# 02-ORIN_LOW_SPEED_SIGNAL.net
KiCad netlist of a schematic drawn in Altium Designer
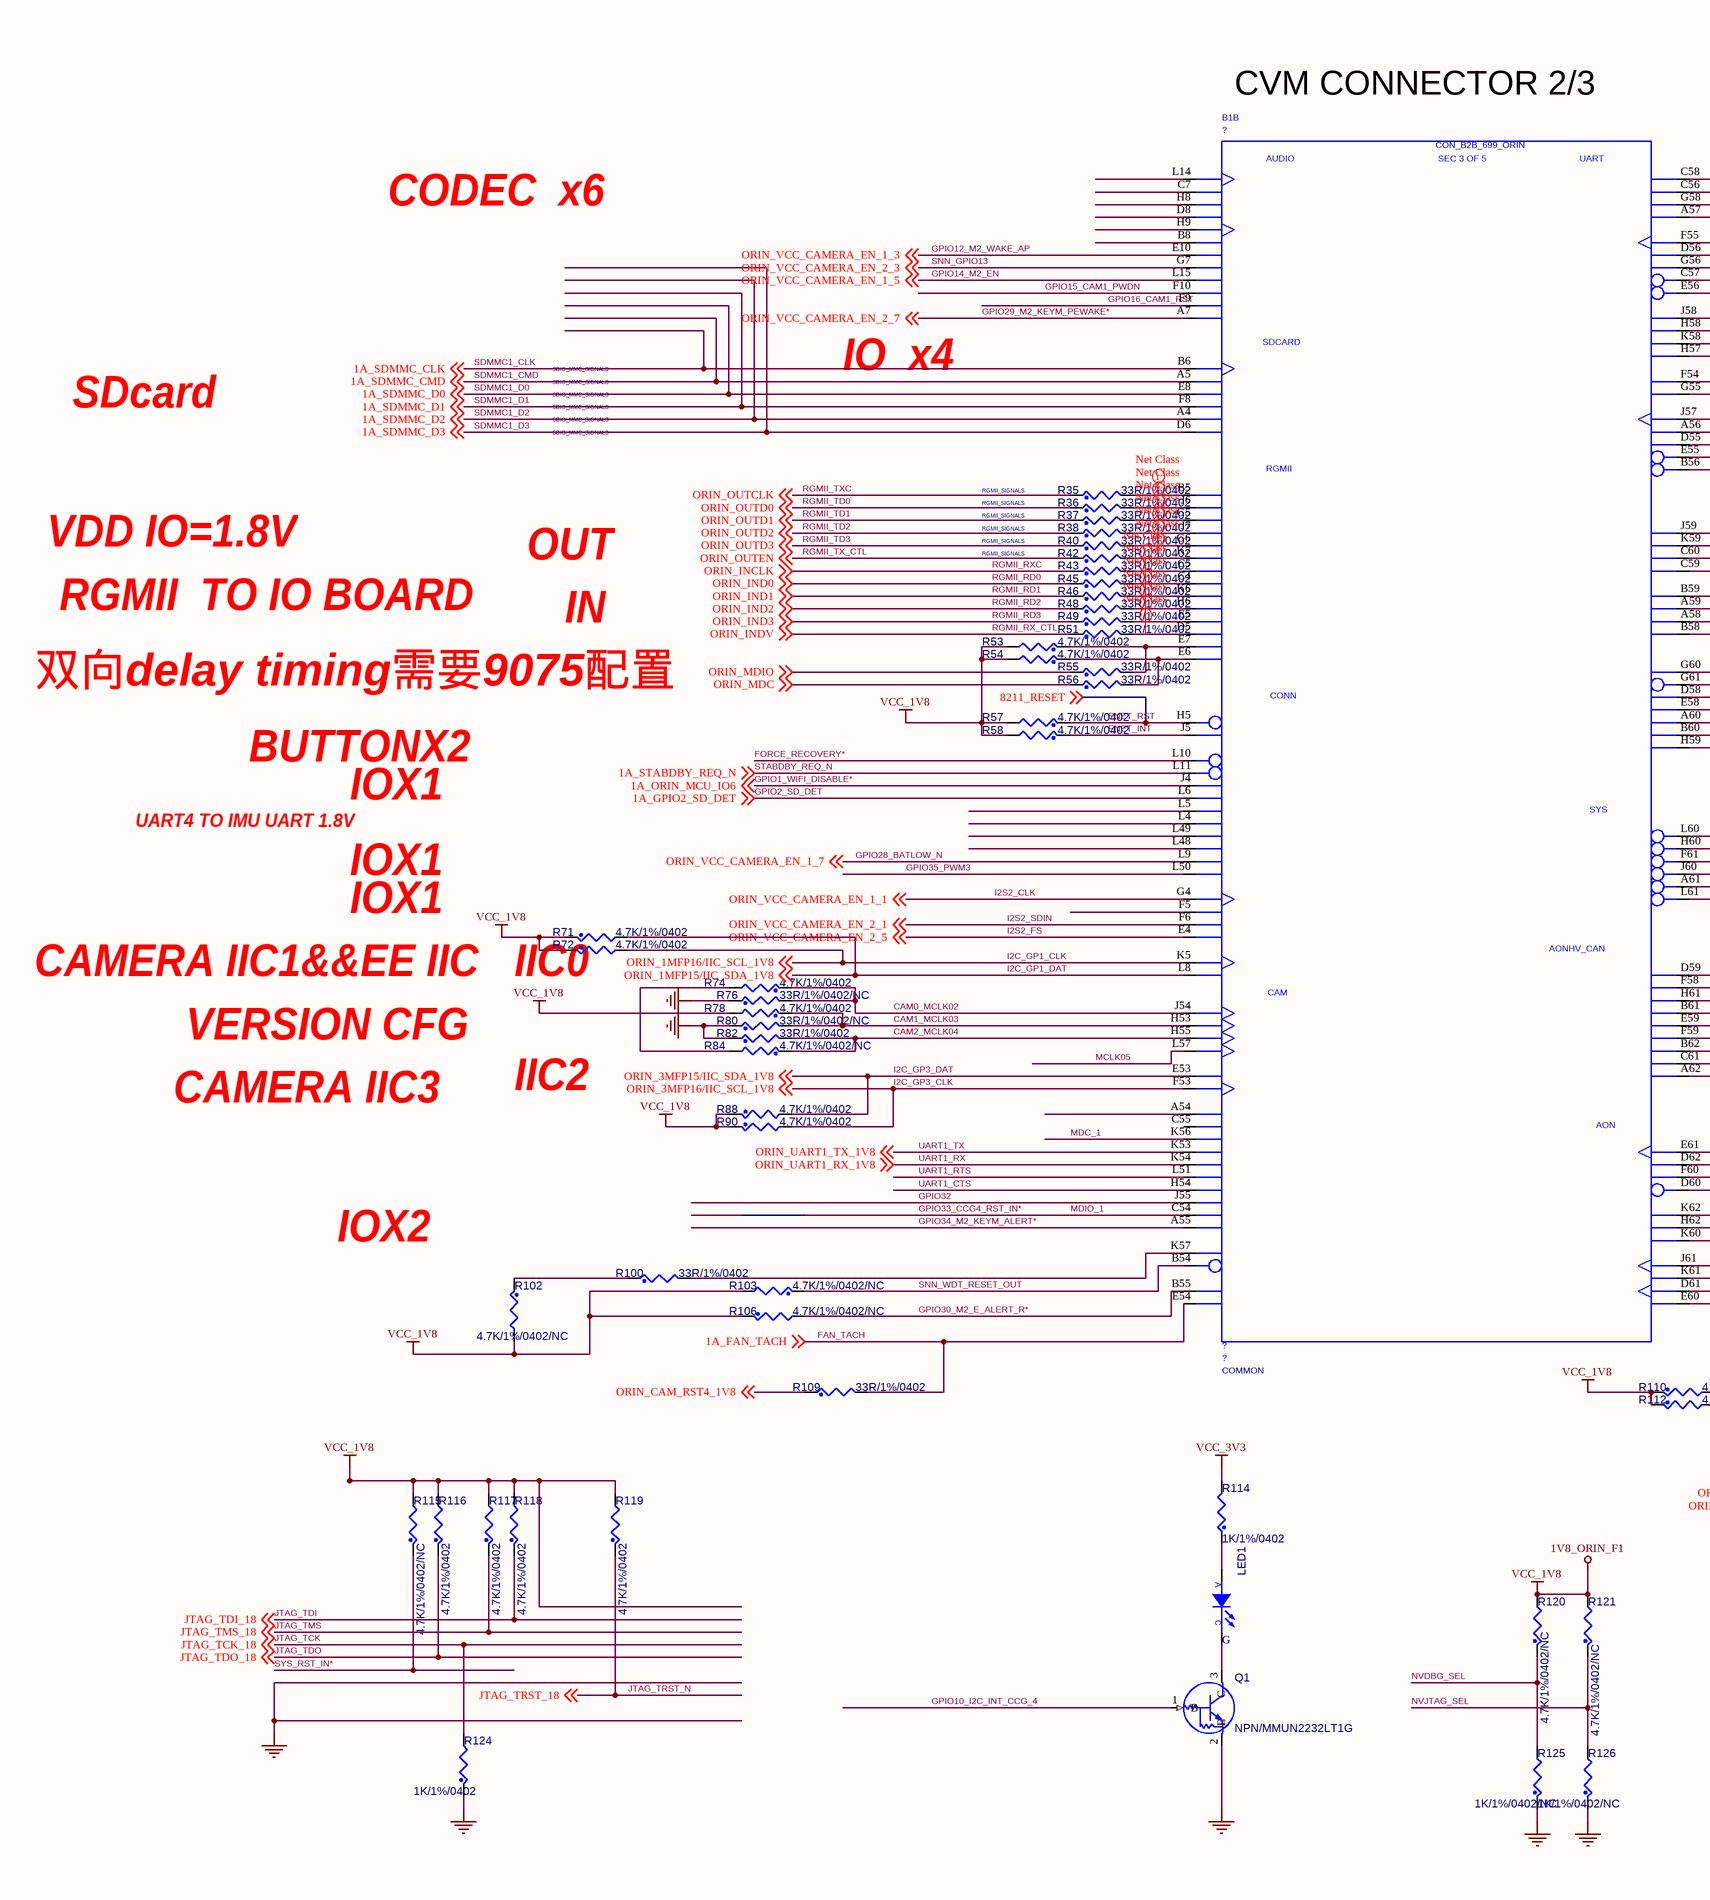
[diagram p0: 02-ORIN_LOW_SPEED_SIGNAL.SchDoc, left]
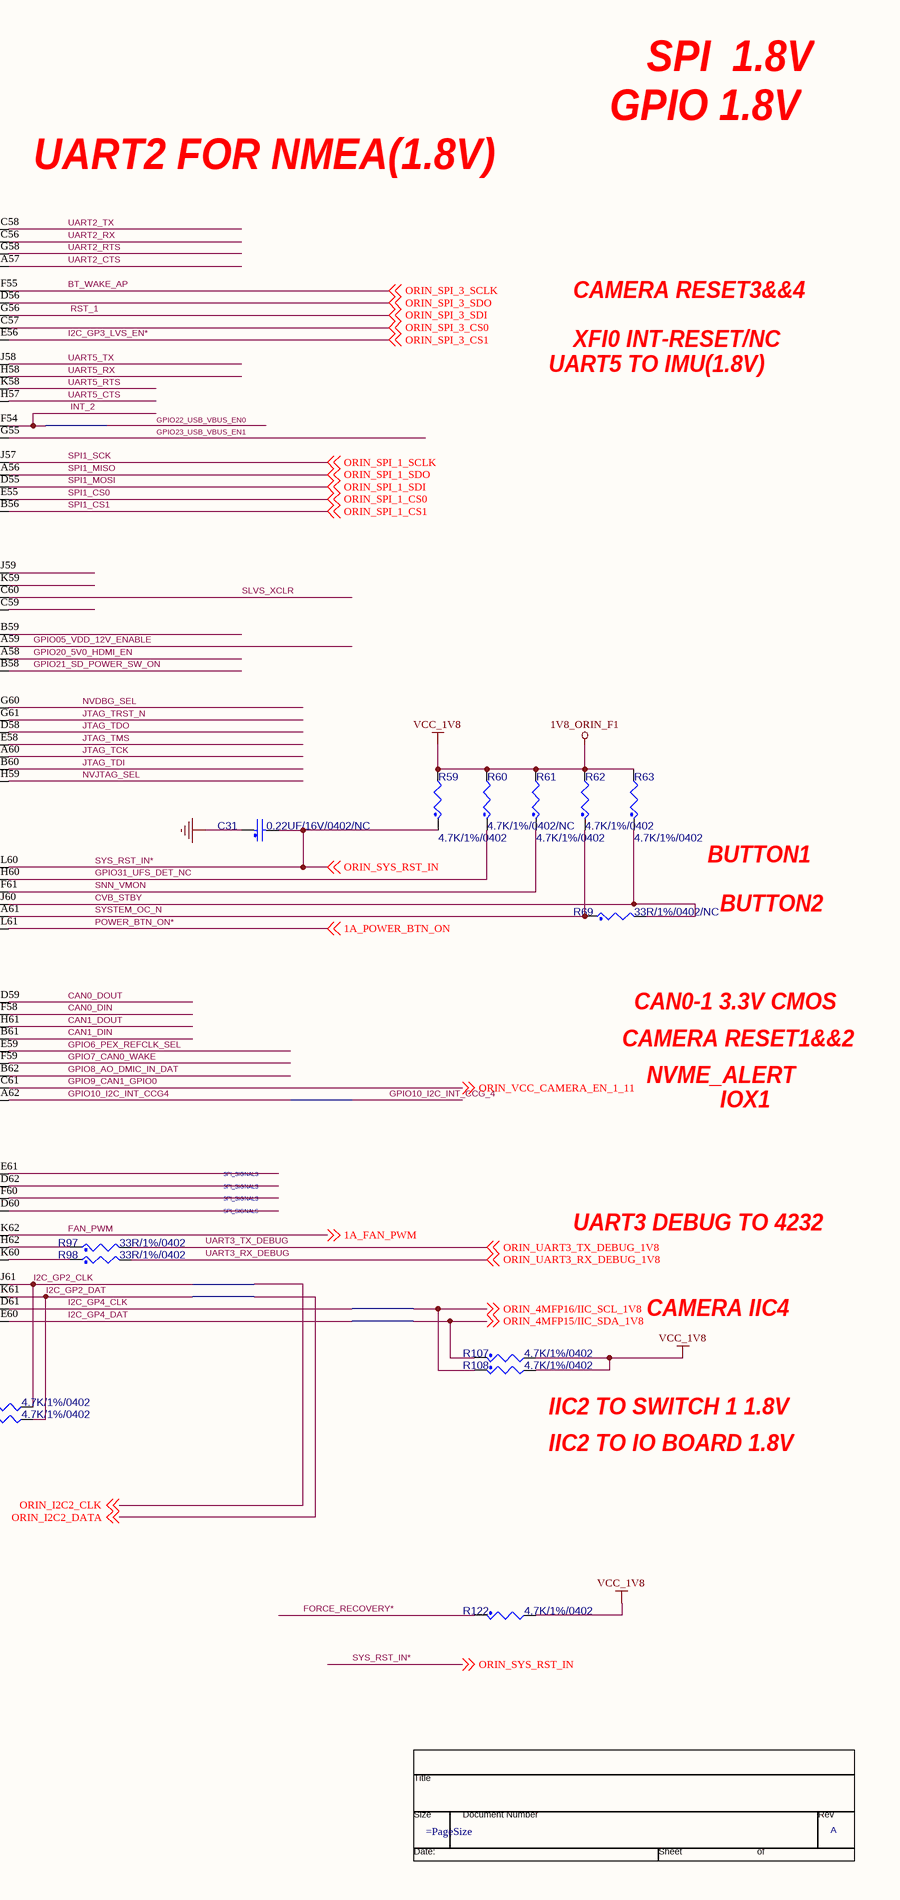
[diagram p1: 02-ORIN_LOW_SPEED_SIGNAL.SchDoc, right]

(export (version "E")
  (design (tool "Eeschema 10.0.6"))
  (components
    (comp (ref "B1")
      (value "CON_B2B_699_ORIN")
      (footprint "CON_MIRMEZ_699_BGA_ST_P009_P013_P015_REVERSE")
      (description "2034560003/MOLEX")
      (fields
        (field (name "DEVICE") "CON_B2B_699_ORIN")
        (field (name "NV_PN") "?")
        (field (name "PACK_TYPE") "?")
        (field (name "PATH") "?")
        (field (name "SKU") "COMMON")
      )
      (libsource (lib "*") (part "CON_B2B_699"))
    )
    (comp (ref "C31")
      (value "0.22UF/16V/0402/NC")
      (footprint "C0402")
      (description "GCM155R71C224KE02/MURATA")
      (fields (field (name "VOLTAGE") "16V") (field (name "TOLERANCE") "10%"))
      (libsource (lib "*") (part "CAP_NP"))
    )
    (comp (ref "LED1")
      (value "LED_P2_Dup1")
      (footprint "LED0603")
      (description "NCD0603G1/NATIONSTAR")
      (fields
        (field (name "VALUE1") "G")
        (field (name "MFR PART NUMBER") "亿光_19-213/G6C-BM1N2B/3T")
        (field (name "PART NUMBER") "20.31.00.0001.02")
      )
      (libsource (lib "*") (part "LED_P2_Dup1"))
    )
    (comp (ref "Q1")
      (value "NPN/MMUN2232LT1G")
      (footprint "SOT23-3-MMUN2232LT1G")
      (description "MMUN2232LT1G/ONSEMI")
      (fields (field (name "Comment") "DTC143ZE"))
      (libsource (lib "*") (part "DTC143ZE"))
    )
    (comp (ref "R35")
      (value "33R/1%/0402")
      (footprint "R0402")
      (description "AC0402FR-0733RL/YAGEO")
      (fields (field (name "TOLERANCE") "1%") (field (name "Comment") "RES_Dup2"))
      (libsource (lib "*") (part "RES_Dup2"))
    )
    (comp (ref "R36")
      (value "33R/1%/0402")
      (footprint "R0402")
      (description "AC0402FR-0733RL/YAGEO")
      (fields (field (name "TOLERANCE") "1%") (field (name "Comment") "RES_Dup2"))
      (libsource (lib "*") (part "RES_Dup2"))
    )
    (comp (ref "R37")
      (value "33R/1%/0402")
      (footprint "R0402")
      (description "AC0402FR-0733RL/YAGEO")
      (fields (field (name "TOLERANCE") "1%") (field (name "Comment") "RES_Dup2"))
      (libsource (lib "*") (part "RES_Dup2"))
    )
    (comp (ref "R38")
      (value "33R/1%/0402")
      (footprint "R0402")
      (description "AC0402FR-0733RL/YAGEO")
      (fields (field (name "TOLERANCE") "1%") (field (name "Comment") "RES_Dup2"))
      (libsource (lib "*") (part "RES_Dup2"))
    )
    (comp (ref "R40")
      (value "33R/1%/0402")
      (footprint "R0402")
      (description "AC0402FR-0733RL/YAGEO")
      (fields (field (name "TOLERANCE") "1%") (field (name "Comment") "RES_Dup2"))
      (libsource (lib "*") (part "RES_Dup2"))
    )
    (comp (ref "R42")
      (value "33R/1%/0402")
      (footprint "R0402")
      (description "AC0402FR-0733RL/YAGEO")
      (fields (field (name "TOLERANCE") "1%") (field (name "Comment") "RES_Dup2"))
      (libsource (lib "*") (part "RES_Dup2"))
    )
    (comp (ref "R43")
      (value "33R/1%/0402")
      (footprint "R0402")
      (description "AC0402FR-0733RL/YAGEO")
      (fields (field (name "TOLERANCE") "1%") (field (name "Comment") "RES_Dup2"))
      (libsource (lib "*") (part "RES_Dup2"))
    )
    (comp (ref "R45")
      (value "33R/1%/0402")
      (footprint "R0402")
      (description "AC0402FR-0733RL/YAGEO")
      (fields (field (name "TOLERANCE") "1%") (field (name "Comment") "RES_Dup2"))
      (libsource (lib "*") (part "RES_Dup2"))
    )
    (comp (ref "R46")
      (value "33R/1%/0402")
      (footprint "R0402")
      (description "AC0402FR-0733RL/YAGEO")
      (fields (field (name "TOLERANCE") "1%") (field (name "Comment") "RES_Dup2"))
      (libsource (lib "*") (part "RES_Dup2"))
    )
    (comp (ref "R48")
      (value "33R/1%/0402")
      (footprint "R0402")
      (description "AC0402FR-0733RL/YAGEO")
      (fields (field (name "TOLERANCE") "1%") (field (name "Comment") "RES_Dup2"))
      (libsource (lib "*") (part "RES_Dup2"))
    )
    (comp (ref "R49")
      (value "33R/1%/0402")
      (footprint "R0402")
      (description "AC0402FR-0733RL/YAGEO")
      (fields (field (name "TOLERANCE") "1%") (field (name "Comment") "RES_Dup2"))
      (libsource (lib "*") (part "RES_Dup2"))
    )
    (comp (ref "R51")
      (value "33R/1%/0402")
      (footprint "R0402")
      (description "AC0402FR-0733RL/YAGEO")
      (fields (field (name "TOLERANCE") "1%") (field (name "Comment") "RES_Dup2"))
      (libsource (lib "*") (part "RES_Dup2"))
    )
    (comp (ref "R53")
      (value "4.7K/1%/0402")
      (footprint "R0402")
      (description "AC0402FR-074K7L/YAGEO")
      (fields (field (name "TOLERANCE") "5%") (field (name "Comment") "RES_Dup2"))
      (libsource (lib "*") (part "RES_Dup2"))
    )
    (comp (ref "R54")
      (value "4.7K/1%/0402")
      (footprint "R0402")
      (description "AC0402FR-074K7L/YAGEO")
      (fields (field (name "TOLERANCE") "5%") (field (name "Comment") "RES_Dup2"))
      (libsource (lib "*") (part "RES_Dup2"))
    )
    (comp (ref "R55")
      (value "33R/1%/0402")
      (footprint "R0402")
      (description "AC0402FR-0733RL/YAGEO")
      (fields (field (name "TOLERANCE") "1%") (field (name "Comment") "RES_Dup2"))
      (libsource (lib "*") (part "RES_Dup2"))
    )
    (comp (ref "R56")
      (value "33R/1%/0402")
      (footprint "R0402")
      (description "AC0402FR-0733RL/YAGEO")
      (fields (field (name "TOLERANCE") "1%") (field (name "Comment") "RES_Dup2"))
      (libsource (lib "*") (part "RES_Dup2"))
    )
    (comp (ref "R57")
      (value "4.7K/1%/0402")
      (footprint "R0402")
      (description "AC0402FR-074K7L/YAGEO")
      (fields (field (name "TOLERANCE") "5%") (field (name "Comment") "RES_Dup2"))
      (libsource (lib "*") (part "RES_Dup2"))
    )
    (comp (ref "R58")
      (value "4.7K/1%/0402")
      (footprint "R0402")
      (description "AC0402FR-074K7L/YAGEO")
      (fields (field (name "TOLERANCE") "5%") (field (name "Comment") "RES_Dup2"))
      (libsource (lib "*") (part "RES_Dup2"))
    )
    (comp (ref "R59")
      (value "4.7K/1%/0402")
      (footprint "R0402")
      (description "AC0402FR-074K7L/YAGEO")
      (fields (field (name "TOLERANCE") "5%") (field (name "Comment") "RES_Dup2"))
      (libsource (lib "*") (part "RES_Dup2"))
    )
    (comp (ref "R60")
      (value "4.7K/1%/0402/NC")
      (footprint "R0402")
      (description "AC0402FR-074K7L/YAGEO")
      (fields (field (name "TOLERANCE") "5%") (field (name "Comment") "RES_Dup2"))
      (libsource (lib "*") (part "RES_Dup2"))
    )
    (comp (ref "R61")
      (value "4.7K/1%/0402")
      (footprint "R0402")
      (description "AC0402FR-074K7L/YAGEO")
      (fields (field (name "TOLERANCE") "5%") (field (name "Comment") "RES_Dup2"))
      (libsource (lib "*") (part "RES_Dup2"))
    )
    (comp (ref "R62")
      (value "4.7K/1%/0402")
      (footprint "R0402")
      (description "AC0402FR-074K7L/YAGEO")
      (fields (field (name "TOLERANCE") "5%") (field (name "Comment") "RES_Dup2"))
      (libsource (lib "*") (part "RES_Dup2"))
    )
    (comp (ref "R63")
      (value "4.7K/1%/0402")
      (footprint "R0402")
      (description "AC0402FR-074K7L/YAGEO")
      (fields (field (name "TOLERANCE") "5%") (field (name "Comment") "RES_Dup2"))
      (libsource (lib "*") (part "RES_Dup2"))
    )
    (comp (ref "R69")
      (value "33R/1%/0402/NC")
      (footprint "R0402")
      (description "AC0402FR-0733RL/YAGEO")
      (fields (field (name "TOLERANCE") "1%") (field (name "Comment") "RES_Dup2"))
      (libsource (lib "*") (part "RES_Dup2"))
    )
    (comp (ref "R71")
      (value "4.7K/1%/0402")
      (footprint "R0402")
      (description "AC0402FR-074K7L/YAGEO")
      (fields (field (name "TOLERANCE") "5%") (field (name "Comment") "RES_Dup2"))
      (libsource (lib "*") (part "RES_Dup2"))
    )
    (comp (ref "R72")
      (value "4.7K/1%/0402")
      (footprint "R0402")
      (description "AC0402FR-074K7L/YAGEO")
      (fields (field (name "TOLERANCE") "5%") (field (name "Comment") "RES_Dup2"))
      (libsource (lib "*") (part "RES_Dup2"))
    )
    (comp (ref "R74")
      (value "4.7K/1%/0402")
      (footprint "R0402")
      (description "AC0402FR-074K7L/YAGEO")
      (fields (field (name "TOLERANCE") "5%") (field (name "Comment") "RES_Dup2"))
      (libsource (lib "*") (part "RES_Dup2"))
    )
    (comp (ref "R76")
      (value "33R/1%/0402/NC")
      (footprint "R0402")
      (description "AC0402FR-0733RL/YAGEO")
      (fields (field (name "TOLERANCE") "1%") (field (name "Comment") "RES_Dup2"))
      (libsource (lib "*") (part "RES_Dup2"))
    )
    (comp (ref "R78")
      (value "4.7K/1%/0402")
      (footprint "R0402")
      (description "AC0402FR-074K7L/YAGEO")
      (fields (field (name "TOLERANCE") "5%") (field (name "Comment") "RES_Dup2"))
      (libsource (lib "*") (part "RES_Dup2"))
    )
    (comp (ref "R80")
      (value "33R/1%/0402/NC")
      (footprint "R0402")
      (description "AC0402FR-0733RL/YAGEO")
      (fields (field (name "TOLERANCE") "1%") (field (name "Comment") "RES_Dup2"))
      (libsource (lib "*") (part "RES_Dup2"))
    )
    (comp (ref "R82")
      (value "33R/1%/0402")
      (footprint "R0402")
      (description "AC0402FR-0733RL/YAGEO")
      (fields (field (name "TOLERANCE") "1%") (field (name "Comment") "RES_Dup2"))
      (libsource (lib "*") (part "RES_Dup2"))
    )
    (comp (ref "R84")
      (value "4.7K/1%/0402/NC")
      (footprint "R0402")
      (description "AC0402FR-074K7L/YAGEO")
      (fields (field (name "TOLERANCE") "5%") (field (name "Comment") "RES_Dup2"))
      (libsource (lib "*") (part "RES_Dup2"))
    )
    (comp (ref "R88")
      (value "4.7K/1%/0402")
      (footprint "R0402")
      (description "AC0402FR-074K7L/YAGEO")
      (fields (field (name "TOLERANCE") "5%") (field (name "Comment") "RES_Dup2"))
      (libsource (lib "*") (part "RES_Dup2"))
    )
    (comp (ref "R90")
      (value "4.7K/1%/0402")
      (footprint "R0402")
      (description "AC0402FR-074K7L/YAGEO")
      (fields (field (name "TOLERANCE") "5%") (field (name "Comment") "RES_Dup2"))
      (libsource (lib "*") (part "RES_Dup2"))
    )
    (comp (ref "R97")
      (value "33R/1%/0402")
      (footprint "R0402")
      (description "AC0402FR-0733RL/YAGEO")
      (fields (field (name "TOLERANCE") "1%") (field (name "Comment") "RES_Dup2"))
      (libsource (lib "*") (part "RES_Dup2"))
    )
    (comp (ref "R98")
      (value "33R/1%/0402")
      (footprint "R0402")
      (description "AC0402FR-0733RL/YAGEO")
      (fields (field (name "TOLERANCE") "1%") (field (name "Comment") "RES_Dup2"))
      (libsource (lib "*") (part "RES_Dup2"))
    )
    (comp (ref "R100")
      (value "33R/1%/0402")
      (footprint "R0402")
      (description "AC0402FR-0733RL/YAGEO")
      (fields (field (name "TOLERANCE") "1%") (field (name "Comment") "RES_Dup2"))
      (libsource (lib "*") (part "RES_Dup2"))
    )
    (comp (ref "R102")
      (value "4.7K/1%/0402/NC")
      (footprint "R0402")
      (description "AC0402FR-074K7L/YAGEO")
      (fields (field (name "TOLERANCE") "5%") (field (name "Comment") "RES_Dup2"))
      (libsource (lib "*") (part "RES_Dup2"))
    )
    (comp (ref "R103")
      (value "4.7K/1%/0402/NC")
      (footprint "R0402")
      (description "AC0402FR-074K7L/YAGEO")
      (fields (field (name "TOLERANCE") "5%") (field (name "Comment") "RES_Dup2"))
      (libsource (lib "*") (part "RES_Dup2"))
    )
    (comp (ref "R106")
      (value "4.7K/1%/0402/NC")
      (footprint "R0402")
      (description "AC0402FR-074K7L/YAGEO")
      (fields (field (name "TOLERANCE") "5%") (field (name "Comment") "RES_Dup2"))
      (libsource (lib "*") (part "RES_Dup2"))
    )
    (comp (ref "R107")
      (value "4.7K/1%/0402")
      (footprint "R0402")
      (description "AC0402FR-074K7L/YAGEO")
      (fields (field (name "TOLERANCE") "5%") (field (name "Comment") "RES_Dup2"))
      (libsource (lib "*") (part "RES_Dup2"))
    )
    (comp (ref "R108")
      (value "4.7K/1%/0402")
      (footprint "R0402")
      (description "AC0402FR-074K7L/YAGEO")
      (fields (field (name "TOLERANCE") "5%") (field (name "Comment") "RES_Dup2"))
      (libsource (lib "*") (part "RES_Dup2"))
    )
    (comp (ref "R109")
      (value "33R/1%/0402")
      (footprint "R0402")
      (description "AC0402FR-0733RL/YAGEO")
      (fields (field (name "TOLERANCE") "1%") (field (name "Comment") "RES_Dup2"))
      (libsource (lib "*") (part "RES_Dup2"))
    )
    (comp (ref "R110")
      (value "4.7K/1%/0402")
      (footprint "R0402")
      (description "AC0402FR-074K7L/YAGEO")
      (fields (field (name "TOLERANCE") "5%") (field (name "Comment") "RES_Dup2"))
      (libsource (lib "*") (part "RES_Dup2"))
    )
    (comp (ref "R112")
      (value "4.7K/1%/0402")
      (footprint "R0402")
      (description "AC0402FR-074K7L/YAGEO")
      (fields (field (name "TOLERANCE") "5%") (field (name "Comment") "RES_Dup2"))
      (libsource (lib "*") (part "RES_Dup2"))
    )
    (comp (ref "R114")
      (value "1K/1%/0402")
      (footprint "R0402")
      (description "AC0402FR-071KL/YAGEO")
      (fields (field (name "TOLERANCE") "5%") (field (name "Comment") "RES_Dup2"))
      (libsource (lib "*") (part "RES_Dup2"))
    )
    (comp (ref "R115")
      (value "4.7K/1%/0402/NC")
      (footprint "R0402")
      (description "AC0402FR-074K7L/YAGEO")
      (fields (field (name "TOLERANCE") "5%") (field (name "Comment") "RES_Dup2"))
      (libsource (lib "*") (part "RES_Dup2"))
    )
    (comp (ref "R116")
      (value "4.7K/1%/0402")
      (footprint "R0402")
      (description "AC0402FR-074K7L/YAGEO")
      (fields (field (name "TOLERANCE") "5%") (field (name "Comment") "RES_Dup2"))
      (libsource (lib "*") (part "RES_Dup2"))
    )
    (comp (ref "R117")
      (value "4.7K/1%/0402")
      (footprint "R0402")
      (description "AC0402FR-074K7L/YAGEO")
      (fields (field (name "TOLERANCE") "5%") (field (name "Comment") "RES_Dup2"))
      (libsource (lib "*") (part "RES_Dup2"))
    )
    (comp (ref "R118")
      (value "4.7K/1%/0402")
      (footprint "R0402")
      (description "AC0402FR-074K7L/YAGEO")
      (fields (field (name "TOLERANCE") "5%") (field (name "Comment") "RES_Dup2"))
      (libsource (lib "*") (part "RES_Dup2"))
    )
    (comp (ref "R119")
      (value "4.7K/1%/0402")
      (footprint "R0402")
      (description "AC0402FR-074K7L/YAGEO")
      (fields (field (name "TOLERANCE") "5%") (field (name "Comment") "RES_Dup2"))
      (libsource (lib "*") (part "RES_Dup2"))
    )
    (comp (ref "R120")
      (value "4.7K/1%/0402/NC")
      (footprint "R0402")
      (description "AC0402FR-074K7L/YAGEO")
      (fields (field (name "TOLERANCE") "5%") (field (name "Comment") "RES_Dup2"))
      (libsource (lib "*") (part "RES_Dup2"))
    )
    (comp (ref "R121")
      (value "4.7K/1%/0402/NC")
      (footprint "R0402")
      (description "AC0402FR-074K7L/YAGEO")
      (fields (field (name "TOLERANCE") "5%") (field (name "Comment") "RES_Dup2"))
      (libsource (lib "*") (part "RES_Dup2"))
    )
    (comp (ref "R122")
      (value "4.7K/1%/0402")
      (footprint "R0402")
      (description "AC0402FR-074K7L/YAGEO")
      (fields (field (name "TOLERANCE") "5%") (field (name "Comment") "RES_Dup2"))
      (libsource (lib "*") (part "RES_Dup2"))
    )
    (comp (ref "R124")
      (value "1K/1%/0402")
      (footprint "R0402")
      (description "AC0402FR-071KL/YAGEO")
      (fields (field (name "TOLERANCE") "5%") (field (name "Comment") "RES_Dup2"))
      (libsource (lib "*") (part "RES_Dup2"))
    )
    (comp (ref "R125")
      (value "1K/1%/0402/NC")
      (footprint "R0402")
      (description "AC0402FR-071KL/YAGEO")
      (fields (field (name "TOLERANCE") "5%") (field (name "Comment") "RES_Dup2"))
      (libsource (lib "*") (part "RES_Dup2"))
    )
    (comp (ref "R126")
      (value "1K/1%/0402/NC")
      (footprint "R0402")
      (description "AC0402FR-071KL/YAGEO")
      (fields (field (name "TOLERANCE") "5%") (field (name "Comment") "RES_Dup2"))
      (libsource (lib "*") (part "RES_Dup2"))
    )
  )
  (nets
    (net (code "1") (name "/CAM0_MCLK02") (class "Default")
      (node (ref "B1") (pin "J54") (pinfunction "MCLK02_J54") (pintype "bidirectional"))
      (node (ref "R74") (pin "1") (pinfunction "1_1") (pintype "passive"))
      (node (ref "R76") (pin "2") (pinfunction "2_2") (pintype "passive"))
    )
    (net (code "2") (name "/CAM1_MCLK03") (class "Default")
      (node (ref "B1") (pin "H53") (pinfunction "MCLK03_H53") (pintype "bidirectional"))
      (node (ref "R78") (pin "1") (pinfunction "1_1") (pintype "passive"))
      (node (ref "R80") (pin "2") (pinfunction "2_2") (pintype "passive"))
    )
    (net (code "3") (name "/CAM2_MCLK04") (class "Default")
      (node (ref "B1") (pin "H55") (pinfunction "MCLK04_H55") (pintype "bidirectional"))
      (node (ref "R82") (pin "2") (pinfunction "2_2") (pintype "passive"))
      (node (ref "R84") (pin "1") (pinfunction "1_1") (pintype "passive"))
    )
    (net (code "4") (name "/CAN0_DIN") (class "Default")
      (node (ref "B1") (pin "F58") (pinfunction "CAN0_DIN_F58") (pintype "bidirectional"))
    )
    (net (code "5") (name "/CAN0_DOUT") (class "Default")
      (node (ref "B1") (pin "D59") (pinfunction "CAN0_DOUT_D59") (pintype "bidirectional"))
    )
    (net (code "6") (name "/CAN1_DIN") (class "Default")
      (node (ref "B1") (pin "B61") (pinfunction "CAN1_DIN_B61") (pintype "bidirectional"))
    )
    (net (code "7") (name "/CAN1_DOUT") (class "Default")
      (node (ref "B1") (pin "H61") (pinfunction "CAN1_DOUT_H61") (pintype "bidirectional"))
    )
    (net (code "8") (name "/CVB_STBY") (class "Default")
      (node (ref "B1") (pin "J60") (pinfunction "STANDBY_ACK_N_J60") (pintype "bidirectional"))
      (node (ref "R63") (pin "1") (pinfunction "1_1") (pintype "passive"))
      (node (ref "R69") (pin "2") (pinfunction "2_2") (pintype "passive"))
    )
    (net (code "9") (name "/ENET_INT") (class "Default")
      (node (ref "B1") (pin "J5") (pinfunction "ENET_INT_J5") (pintype "bidirectional"))
      (node (ref "R58") (pin "1") (pinfunction "1_1") (pintype "passive"))
    )
    (net (code "10") (name "/FORCE_RECOVERY*") (class "Default")
      (node (ref "B1") (pin "L10") (pinfunction "FORCE_RECOVERY_N_L10") (pintype "bidirectional"))
      (node (ref "R122") (pin "1") (pinfunction "1_1") (pintype "passive"))
    )
    (net (code "11") (name "/GPIO05_VDD_12V_ENABLE") (class "Default")
      (node (ref "B1") (pin "A59") (pinfunction "GPIO05_A59") (pintype "bidirectional"))
    )
    (net (code "12") (name "/GPIO6_PEX_REFCLK_SEL") (class "Default")
      (node (ref "B1") (pin "E59") (pinfunction "GPIO06_E59") (pintype "bidirectional"))
    )
    (net (code "13") (name "/GPIO7_CAN0_WAKE") (class "Default")
      (node (ref "B1") (pin "F59") (pinfunction "GPIO07_F59") (pintype "bidirectional"))
    )
    (net (code "14") (name "/GPIO8_AO_DMIC_IN_DAT") (class "Default")
      (node (ref "B1") (pin "B62") (pinfunction "GPIO08_B62") (pintype "bidirectional"))
    )
    (net (code "15") (name "/GPIO10_I2C_INT_CCG4") (class "Default")
      (node (ref "B1") (pin "A62") (pinfunction "GPIO10_A62") (pintype "bidirectional"))
      (node (ref "Q1") (pin "1") (pinfunction "B_1") (pintype "input"))
    )
    (net (code "16") (name "/GPIO15_CAM1_PWDN") (class "Default")
      (node (ref "B1") (pin "F10") (pinfunction "GPIO15_F10") (pintype "bidirectional"))
    )
    (net (code "17") (name "/GPIO16_CAM1_RST") (class "Default")
      (node (ref "B1") (pin "F9") (pinfunction "GPIO16_F9") (pintype "bidirectional"))
    )
    (net (code "18") (name "/GPIO20_5V0_HDMI_EN") (class "Default")
      (node (ref "B1") (pin "A58") (pinfunction "GPIO20_A58") (pintype "bidirectional"))
    )
    (net (code "19") (name "/GPIO21_SD_POWER_SW_ON") (class "Default")
      (node (ref "B1") (pin "B58") (pinfunction "GPIO21_B58") (pintype "bidirectional"))
    )
    (net (code "20") (name "/GPIO22_USB_VBUS_EN0") (class "Default")
      (node (ref "B1") (pin "F54") (pinfunction "GPIO22_F54") (pintype "bidirectional"))
    )
    (net (code "21") (name "/GPIO23_USB_VBUS_EN1") (class "Default")
      (node (ref "B1") (pin "G55") (pinfunction "GPIO23_G55") (pintype "bidirectional"))
    )
    (net (code "22") (name "/GPIO30_M2_E_ALERT_R*") (class "Default")
      (node (ref "B1") (pin "B55") (pinfunction "GPIO30_B55") (pintype "bidirectional"))
      (node (ref "R106") (pin "2") (pinfunction "2_2") (pintype "passive"))
    )
    (net (code "23") (name "/GPIO31_UFS_DET_NC") (class "Default")
      (node (ref "B1") (pin "H60") (pinfunction "GPIO31_H60") (pintype "bidirectional"))
      (node (ref "R60") (pin "1") (pinfunction "1_1") (pintype "passive"))
    )
    (net (code "24") (name "/GPIO32") (class "Default")
      (node (ref "B1") (pin "J55") (pinfunction "GPIO32_J55") (pintype "bidirectional"))
    )
    (net (code "25") (name "/GPIO33_CCG4_RST_IN*") (class "Default")
      (node (ref "B1") (pin "C54") (pinfunction "GPIO33_C54") (pintype "bidirectional"))
    )
    (net (code "26") (name "/GPIO34_M2_KEYM_ALERT*") (class "Default")
      (node (ref "B1") (pin "A55") (pinfunction "GPIO34_A55") (pintype "bidirectional"))
    )
    (net (code "27") (name "/GPIO35_PWM3") (class "Default")
      (node (ref "B1") (pin "L50") (pinfunction "GPIO35_L50") (pintype "bidirectional"))
    )
    (net (code "28") (name "/MCLK05") (class "Default")
      (node (ref "B1") (pin "L57") (pinfunction "MCLK05_L57") (pintype "bidirectional"))
    )
    (net (code "29") (name "/MDC_1") (class "Default")
      (node (ref "B1") (pin "K56") (pinfunction "GPIO19_K56") (pintype "bidirectional"))
    )
    (net (code "30") (name "/NVDBG_SEL") (class "Default")
      (node (ref "B1") (pin "G60") (pinfunction "NVDBG_SEL_G60") (pintype "bidirectional"))
      (node (ref "R120") (pin "1") (pinfunction "1_1") (pintype "passive"))
      (node (ref "R125") (pin "2") (pinfunction "2_2") (pintype "passive"))
    )
    (net (code "31") (name "/NVJTAG_SEL") (class "Default")
      (node (ref "B1") (pin "H59") (pinfunction "NVJTAG_SEL_H59") (pintype "bidirectional"))
      (node (ref "R121") (pin "1") (pinfunction "1_1") (pintype "passive"))
      (node (ref "R126") (pin "2") (pinfunction "2_2") (pintype "passive"))
    )
    (net (code "32") (name "/SLVS_XCLR") (class "Default")
      (node (ref "B1") (pin "C60") (pinfunction "I2S3_FS_C60") (pintype "bidirectional"))
    )
    (net (code "33") (name "/SNN_VMON") (class "Default")
      (node (ref "B1") (pin "F61") (pinfunction "VCOMP_ALERT_N_F61") (pintype "bidirectional"))
      (node (ref "R61") (pin "1") (pinfunction "1_1") (pintype "passive"))
    )
    (net (code "34") (name "/SNN_WDT_RESET_OUT") (class "Default")
      (node (ref "B1") (pin "B54") (pinfunction "WDT_RESET_OUT_N_B54") (pintype "bidirectional"))
      (node (ref "R103") (pin "1") (pinfunction "1_1") (pintype "passive"))
    )
    (net (code "35") (name "/SYSTEM_OC_N") (class "Default")
      (node (ref "B1") (pin "A61") (pinfunction "SYSTEM_OC_N_A61") (pintype "bidirectional"))
      (node (ref "R62") (pin "1") (pinfunction "1_1") (pintype "passive"))
      (node (ref "R69") (pin "1") (pinfunction "1_1") (pintype "passive"))
    )
    (net (code "36") (name "/UART1_CTS") (class "Default")
      (node (ref "B1") (pin "H54") (pinfunction "UART1_CTS_H54") (pintype "bidirectional"))
    )
    (net (code "37") (name "/UART1_RTS") (class "Default")
      (node (ref "B1") (pin "L51") (pinfunction "UART1_RTS_L51") (pintype "bidirectional"))
    )
    (net (code "38") (name "/UART2_CTS") (class "Default")
      (node (ref "B1") (pin "A57") (pinfunction "UART2_CTS_A57") (pintype "bidirectional"))
    )
    (net (code "39") (name "/UART2_RTS") (class "Default")
      (node (ref "B1") (pin "G58") (pinfunction "UART2_RTS_G58") (pintype "bidirectional"))
    )
    (net (code "40") (name "/UART2_RX") (class "Default")
      (node (ref "B1") (pin "C56") (pinfunction "UART2_RX_C56") (pintype "bidirectional"))
    )
    (net (code "41") (name "/UART2_TX") (class "Default")
      (node (ref "B1") (pin "C58") (pinfunction "UART2_TX_C58") (pintype "bidirectional"))
    )
    (net (code "42") (name "/UART5_CTS") (class "Default")
      (node (ref "B1") (pin "H57") (pinfunction "UART5_CTS_H57") (pintype "bidirectional"))
    )
    (net (code "43") (name "/UART5_RTS") (class "Default")
      (node (ref "B1") (pin "K58") (pinfunction "UART5_RTS_K58") (pintype "bidirectional"))
    )
    (net (code "44") (name "/UART5_RX") (class "Default")
      (node (ref "B1") (pin "H58") (pinfunction "UART5_RX_H58") (pintype "bidirectional"))
    )
    (net (code "45") (name "/UART5_TX") (class "Default")
      (node (ref "B1") (pin "J58") (pinfunction "UART5_TX_J58") (pintype "bidirectional"))
    )
    (net (code "46") (name "1A_FAN_PWM") (class "Default")
      (node (ref "B1") (pin "K62") (pinfunction "FAN_PWM_K62") (pintype "bidirectional"))
    )
    (net (code "47") (name "1A_FAN_TACH") (class "Default")
      (node (ref "B1") (pin "E54") (pinfunction "FAN_TACH_E54") (pintype "bidirectional"))
      (node (ref "R109") (pin "2") (pinfunction "2_2") (pintype "passive"))
    )
    (net (code "48") (name "1A_GPIO2_SD_DET") (class "Default")
      (node (ref "B1") (pin "L6") (pinfunction "GPIO02_L6") (pintype "bidirectional"))
    )
    (net (code "49") (name "1A_ORIN_MCU_IO6") (class "Default")
      (node (ref "B1") (pin "J4") (pinfunction "GPIO01_J4") (pintype "bidirectional"))
    )
    (net (code "50") (name "1A_POWER_BTN_ON") (class "Default")
      (node (ref "B1") (pin "L61") (pinfunction "POWER_BTN_N_L61") (pintype "bidirectional"))
    )
    (net (code "51") (name "1A_SDMMC_CLK") (class "Default")
      (node (ref "B1") (pin "B6") (pinfunction "SDCARD_CLK_B6") (pintype "bidirectional"))
    )
    (net (code "52") (name "1A_SDMMC_CMD") (class "Default")
      (node (ref "B1") (pin "A5") (pinfunction "SDCARD_CMD_A5") (pintype "bidirectional"))
    )
    (net (code "53") (name "1A_SDMMC_D0") (class "Default")
      (node (ref "B1") (pin "E8") (pinfunction "SDCARD_D0_E8") (pintype "bidirectional"))
    )
    (net (code "54") (name "1A_SDMMC_D1") (class "Default")
      (node (ref "B1") (pin "F8") (pinfunction "SDCARD_D1_F8") (pintype "bidirectional"))
    )
    (net (code "55") (name "1A_SDMMC_D2") (class "Default")
      (node (ref "B1") (pin "A4") (pinfunction "SDCARD_D2_A4") (pintype "bidirectional"))
    )
    (net (code "56") (name "1A_SDMMC_D3") (class "Default")
      (node (ref "B1") (pin "D6") (pinfunction "SDCARD_D3_D6") (pintype "bidirectional"))
    )
    (net (code "57") (name "1A_STABDBY_REQ_N") (class "Default")
      (node (ref "B1") (pin "L11") (pinfunction "STANDBY_REQ_N_L11") (pintype "bidirectional"))
    )
    (net (code "58") (name "1V8_ORIN_F1") (class "Default")
      (node (ref "R102") (pin "2") (pinfunction "2_2") (pintype "passive"))
      (node (ref "R103") (pin "2") (pinfunction "2_2") (pintype "passive"))
      (node (ref "R106") (pin "1") (pinfunction "1_1") (pintype "passive"))
      (node (ref "R107") (pin "2") (pinfunction "2_2") (pintype "passive"))
      (node (ref "R108") (pin "2") (pinfunction "2_2") (pintype "passive"))
      (node (ref "R110") (pin "1") (pinfunction "1_1") (pintype "passive"))
      (node (ref "R112") (pin "1") (pinfunction "1_1") (pintype "passive"))
      (node (ref "R115") (pin "2") (pinfunction "2_2") (pintype "passive"))
      (node (ref "R116") (pin "2") (pinfunction "2_2") (pintype "passive"))
      (node (ref "R117") (pin "2") (pinfunction "2_2") (pintype "passive"))
      (node (ref "R118") (pin "2") (pinfunction "2_2") (pintype "passive"))
      (node (ref "R119") (pin "2") (pinfunction "2_2") (pintype "passive"))
      (node (ref "R120") (pin "2") (pinfunction "2_2") (pintype "passive"))
      (node (ref "R121") (pin "2") (pinfunction "2_2") (pintype "passive"))
      (node (ref "R122") (pin "2") (pinfunction "2_2") (pintype "passive"))
      (node (ref "R53") (pin "2") (pinfunction "2_2") (pintype "passive"))
      (node (ref "R54") (pin "2") (pinfunction "2_2") (pintype "passive"))
      (node (ref "R57") (pin "2") (pinfunction "2_2") (pintype "passive"))
      (node (ref "R58") (pin "2") (pinfunction "2_2") (pintype "passive"))
      (node (ref "R59") (pin "2") (pinfunction "2_2") (pintype "passive"))
      (node (ref "R60") (pin "2") (pinfunction "2_2") (pintype "passive"))
      (node (ref "R61") (pin "2") (pinfunction "2_2") (pintype "passive"))
      (node (ref "R62") (pin "2") (pinfunction "2_2") (pintype "passive"))
      (node (ref "R63") (pin "2") (pinfunction "2_2") (pintype "passive"))
      (node (ref "R71") (pin "1") (pinfunction "1_1") (pintype "passive"))
      (node (ref "R72") (pin "1") (pinfunction "1_1") (pintype "passive"))
      (node (ref "R78") (pin "2") (pinfunction "2_2") (pintype "passive"))
      (node (ref "R88") (pin "1") (pinfunction "1_1") (pintype "passive"))
      (node (ref "R90") (pin "1") (pinfunction "1_1") (pintype "passive"))
    )
    (net (code "59") (name "8211_RESET") (class "Default")
      (node (ref "B1") (pin "H5") (pinfunction "ENET_RST_N_H5") (pintype "bidirectional"))
      (node (ref "R57") (pin "1") (pinfunction "1_1") (pintype "passive"))
    )
    (net (code "60") (name "GND") (class "Default")
      (node (ref "C31") (pin "1") (pinfunction "1_1") (pintype "passive"))
      (node (ref "Q1") (pin "2") (pinfunction "E_2") (pintype "passive"))
      (node (ref "R124") (pin "1") (pinfunction "1_1") (pintype "passive"))
      (node (ref "R125") (pin "1") (pinfunction "1_1") (pintype "passive"))
      (node (ref "R126") (pin "1") (pinfunction "1_1") (pintype "passive"))
      (node (ref "R76") (pin "1") (pinfunction "1_1") (pintype "passive"))
      (node (ref "R80") (pin "1") (pinfunction "1_1") (pintype "passive"))
      (node (ref "R82") (pin "1") (pinfunction "1_1") (pintype "passive"))
    )
    (net (code "61") (name "JTAG_TCK_18") (class "Default")
      (node (ref "B1") (pin "A60") (pinfunction "JTAG_TCK_A60") (pintype "bidirectional"))
      (node (ref "R124") (pin "2") (pinfunction "2_2") (pintype "passive"))
    )
    (net (code "62") (name "JTAG_TDI_18") (class "Default")
      (node (ref "B1") (pin "B60") (pinfunction "JTAG_TDI_B60") (pintype "bidirectional"))
      (node (ref "R118") (pin "1") (pinfunction "1_1") (pintype "passive"))
    )
    (net (code "63") (name "JTAG_TDO_18") (class "Default")
      (node (ref "B1") (pin "D58") (pinfunction "JTAG_TDO_D58") (pintype "bidirectional"))
      (node (ref "R116") (pin "1") (pinfunction "1_1") (pintype "passive"))
    )
    (net (code "64") (name "JTAG_TMS_18") (class "Default")
      (node (ref "B1") (pin "E58") (pinfunction "JTAG_TMS_E58") (pintype "bidirectional"))
      (node (ref "R117") (pin "1") (pinfunction "1_1") (pintype "passive"))
    )
    (net (code "65") (name "JTAG_TRST_18") (class "Default")
      (node (ref "B1") (pin "G61") (pinfunction "JTAG_TRST_N_G61") (pintype "bidirectional"))
      (node (ref "R119") (pin "1") (pinfunction "1_1") (pintype "passive"))
    )
    (net (code "66") (name "Net-(B1B-PWM01)") (class "Default")
      (node (ref "B1") (pin "K57") (pinfunction "PWM01_K57") (pintype "bidirectional"))
      (node (ref "R100") (pin "2") (pinfunction "2_2") (pintype "passive"))
    )
    (net (code "67") (name "Net-(B1B-RGMII_RD0)") (class "Default")
      (node (ref "B1") (pin "C4") (pinfunction "RGMII_RD0_C4") (pintype "bidirectional"))
      (node (ref "R45") (pin "2") (pinfunction "2_2") (pintype "passive"))
    )
    (net (code "68") (name "Net-(B1B-RGMII_RD1)") (class "Default")
      (node (ref "B1") (pin "K6") (pinfunction "RGMII_RD1_K6") (pintype "bidirectional"))
      (node (ref "R46") (pin "2") (pinfunction "2_2") (pintype "passive"))
    )
    (net (code "69") (name "Net-(B1B-RGMII_RD2)") (class "Default")
      (node (ref "B1") (pin "H6") (pinfunction "RGMII_RD2_H6") (pintype "bidirectional"))
      (node (ref "R48") (pin "2") (pinfunction "2_2") (pintype "passive"))
    )
    (net (code "70") (name "Net-(B1B-RGMII_RD3)") (class "Default")
      (node (ref "B1") (pin "E5") (pinfunction "RGMII_RD3_E5") (pintype "bidirectional"))
      (node (ref "R49") (pin "2") (pinfunction "2_2") (pintype "passive"))
    )
    (net (code "71") (name "Net-(B1B-RGMII_RXC)") (class "Default")
      (node (ref "B1") (pin "C5") (pinfunction "RGMII_RXC_C5") (pintype "bidirectional"))
      (node (ref "R43") (pin "2") (pinfunction "2_2") (pintype "passive"))
    )
    (net (code "72") (name "Net-(B1B-RGMII_RX_CTL)") (class "Default")
      (node (ref "B1") (pin "D5") (pinfunction "RGMII_RX_CTL_D5") (pintype "bidirectional"))
      (node (ref "R51") (pin "2") (pinfunction "2_2") (pintype "passive"))
    )
    (net (code "73") (name "Net-(B1B-RGMII_SMA_MDC)") (class "Default")
      (node (ref "B1") (pin "E6") (pinfunction "RGMII_SMA_MDC_E6") (pintype "bidirectional"))
      (node (ref "R54") (pin "1") (pinfunction "1_1") (pintype "passive"))
      (node (ref "R56") (pin "2") (pinfunction "2_2") (pintype "passive"))
    )
    (net (code "74") (name "Net-(B1B-RGMII_SMA_MDIO)") (class "Default")
      (node (ref "B1") (pin "E7") (pinfunction "RGMII_SMA_MDIO_E7") (pintype "bidirectional"))
      (node (ref "R53") (pin "1") (pinfunction "1_1") (pintype "passive"))
      (node (ref "R55") (pin "2") (pinfunction "2_2") (pintype "passive"))
    )
    (net (code "75") (name "Net-(B1B-RGMII_TD0)") (class "Default")
      (node (ref "B1") (pin "J6") (pinfunction "RGMII_TD0_J6") (pintype "bidirectional"))
      (node (ref "R36") (pin "2") (pinfunction "2_2") (pintype "passive"))
    )
    (net (code "76") (name "Net-(B1B-RGMII_TD1)") (class "Default")
      (node (ref "B1") (pin "G5") (pinfunction "RGMII_TD1_G5") (pintype "bidirectional"))
      (node (ref "R37") (pin "2") (pinfunction "2_2") (pintype "passive"))
    )
    (net (code "77") (name "Net-(B1B-RGMII_TD2)") (class "Default")
      (node (ref "B1") (pin "J7") (pinfunction "RGMII_TD2_J7") (pintype "bidirectional"))
      (node (ref "R38") (pin "2") (pinfunction "2_2") (pintype "passive"))
    )
    (net (code "78") (name "Net-(B1B-RGMII_TD3)") (class "Default")
      (node (ref "B1") (pin "G6") (pinfunction "RGMII_TD3_G6") (pintype "bidirectional"))
      (node (ref "R40") (pin "2") (pinfunction "2_2") (pintype "passive"))
    )
    (net (code "79") (name "Net-(B1B-RGMII_TXC)") (class "Default")
      (node (ref "B1") (pin "B5") (pinfunction "RGMII_TXC_B5") (pintype "bidirectional"))
      (node (ref "R35") (pin "2") (pinfunction "2_2") (pintype "passive"))
    )
    (net (code "80") (name "Net-(B1B-RGMII_TX_CTL)") (class "Default")
      (node (ref "B1") (pin "K7") (pinfunction "RGMII_TX_CTL_K7") (pintype "bidirectional"))
      (node (ref "R42") (pin "2") (pinfunction "2_2") (pintype "passive"))
    )
    (net (code "81") (name "Net-(B1B-UART3_RX_DEBUG)") (class "Default")
      (node (ref "B1") (pin "K60") (pinfunction "UART3_RX_DEBUG_K60") (pintype "bidirectional"))
      (node (ref "R98") (pin "1") (pinfunction "1_1") (pintype "passive"))
    )
    (net (code "82") (name "Net-(B1B-UART3_TX_DEBUG)") (class "Default")
      (node (ref "B1") (pin "H62") (pinfunction "UART3_TX_DEBUG_H62") (pintype "bidirectional"))
      (node (ref "R97") (pin "1") (pinfunction "1_1") (pintype "passive"))
    )
    (net (code "83") (name "Net-(LED1-ANODE)") (class "Default")
      (node (ref "LED1") (pin "1") (pinfunction "ANODE_1") (pintype "passive"))
      (node (ref "R114") (pin "1") (pinfunction "1_1") (pintype "passive"))
    )
    (net (code "84") (name "Net-(LED1-CATHODE)") (class "Default")
      (node (ref "LED1") (pin "2") (pinfunction "CATHODE_2") (pintype "passive"))
      (node (ref "Q1") (pin "3") (pinfunction "C_3") (pintype "passive"))
    )
    (net (code "85") (name "Net-(R74-Pad2)") (class "Default")
      (node (ref "R74") (pin "2") (pinfunction "2_2") (pintype "passive"))
      (node (ref "R84") (pin "2") (pinfunction "2_2") (pintype "passive"))
    )
    (net (code "86") (name "Net-(R100-Pad1)") (class "Default")
      (node (ref "R100") (pin "1") (pinfunction "1_1") (pintype "passive"))
      (node (ref "R102") (pin "1") (pinfunction "1_1") (pintype "passive"))
    )
    (net (code "87") (name "ORIN_1MFP15{slash}IIC_SDA_1V8") (class "Default")
      (node (ref "B1") (pin "L8") (pinfunction "I2C1_DAT_L8") (pintype "bidirectional"))
      (node (ref "R71") (pin "2") (pinfunction "2_2") (pintype "passive"))
    )
    (net (code "88") (name "ORIN_1MFP16{slash}IIC_SCL_1V8") (class "Default")
      (node (ref "B1") (pin "K5") (pinfunction "I2C1_CLK_K5") (pintype "bidirectional"))
      (node (ref "R72") (pin "2") (pinfunction "2_2") (pintype "passive"))
    )
    (net (code "89") (name "ORIN_3MFP15{slash}IIC_SDA_1V8") (class "Default")
      (node (ref "B1") (pin "E53") (pinfunction "I2C3_DAT_E53") (pintype "bidirectional"))
      (node (ref "R88") (pin "2") (pinfunction "2_2") (pintype "passive"))
    )
    (net (code "90") (name "ORIN_3MFP16{slash}IIC_SCL_1V8") (class "Default")
      (node (ref "B1") (pin "F53") (pinfunction "I2C3_CLK_F53") (pintype "bidirectional"))
      (node (ref "R90") (pin "2") (pinfunction "2_2") (pintype "passive"))
    )
    (net (code "91") (name "ORIN_4MFP15{slash}IIC_SDA_1V8") (class "Default")
      (node (ref "B1") (pin "E60") (pinfunction "I2C4_DAT_E60") (pintype "bidirectional"))
      (node (ref "R107") (pin "1") (pinfunction "1_1") (pintype "passive"))
    )
    (net (code "92") (name "ORIN_4MFP16{slash}IIC_SCL_1V8") (class "Default")
      (node (ref "B1") (pin "D61") (pinfunction "I2C4_CLK_D61") (pintype "bidirectional"))
      (node (ref "R108") (pin "1") (pinfunction "1_1") (pintype "passive"))
    )
    (net (code "93") (name "ORIN_CAM_RST4_1V8") (class "Default")
      (node (ref "R109") (pin "1") (pinfunction "1_1") (pintype "passive"))
    )
    (net (code "94") (name "ORIN_I2C2_CLK") (class "Default")
      (node (ref "B1") (pin "J61") (pinfunction "I2C2_CLK_J61") (pintype "bidirectional"))
      (node (ref "R110") (pin "2") (pinfunction "2_2") (pintype "passive"))
    )
    (net (code "95") (name "ORIN_I2C2_DATA") (class "Default")
      (node (ref "B1") (pin "K61") (pinfunction "I2C2_DAT_K61") (pintype "bidirectional"))
      (node (ref "R112") (pin "2") (pinfunction "2_2") (pintype "passive"))
    )
    (net (code "96") (name "ORIN_INCLK") (class "Default")
      (node (ref "R43") (pin "1") (pinfunction "1_1") (pintype "passive"))
    )
    (net (code "97") (name "ORIN_IND0") (class "Default")
      (node (ref "R45") (pin "1") (pinfunction "1_1") (pintype "passive"))
    )
    (net (code "98") (name "ORIN_IND1") (class "Default")
      (node (ref "R46") (pin "1") (pinfunction "1_1") (pintype "passive"))
    )
    (net (code "99") (name "ORIN_IND2") (class "Default")
      (node (ref "R48") (pin "1") (pinfunction "1_1") (pintype "passive"))
    )
    (net (code "100") (name "ORIN_IND3") (class "Default")
      (node (ref "R49") (pin "1") (pinfunction "1_1") (pintype "passive"))
    )
    (net (code "101") (name "ORIN_INDV") (class "Default")
      (node (ref "R51") (pin "1") (pinfunction "1_1") (pintype "passive"))
    )
    (net (code "102") (name "ORIN_MDC") (class "Default")
      (node (ref "R56") (pin "1") (pinfunction "1_1") (pintype "passive"))
    )
    (net (code "103") (name "ORIN_MDIO") (class "Default")
      (node (ref "R55") (pin "1") (pinfunction "1_1") (pintype "passive"))
    )
    (net (code "104") (name "ORIN_OUTCLK") (class "Default")
      (node (ref "R35") (pin "1") (pinfunction "1_1") (pintype "passive"))
    )
    (net (code "105") (name "ORIN_OUTD0") (class "Default")
      (node (ref "R36") (pin "1") (pinfunction "1_1") (pintype "passive"))
    )
    (net (code "106") (name "ORIN_OUTD1") (class "Default")
      (node (ref "R37") (pin "1") (pinfunction "1_1") (pintype "passive"))
    )
    (net (code "107") (name "ORIN_OUTD2") (class "Default")
      (node (ref "R38") (pin "1") (pinfunction "1_1") (pintype "passive"))
    )
    (net (code "108") (name "ORIN_OUTD3") (class "Default")
      (node (ref "R40") (pin "1") (pinfunction "1_1") (pintype "passive"))
    )
    (net (code "109") (name "ORIN_OUTEN") (class "Default")
      (node (ref "R42") (pin "1") (pinfunction "1_1") (pintype "passive"))
    )
    (net (code "110") (name "ORIN_SPI_1_CS0") (class "Default")
      (node (ref "B1") (pin "E55") (pinfunction "SPI1_CS0_N_E55") (pintype "bidirectional"))
    )
    (net (code "111") (name "ORIN_SPI_1_CS1") (class "Default")
      (node (ref "B1") (pin "B56") (pinfunction "SPI1_CS1_N_B56") (pintype "bidirectional"))
    )
    (net (code "112") (name "ORIN_SPI_1_SCLK") (class "Default")
      (node (ref "B1") (pin "J57") (pinfunction "SPI1_CLK_J57") (pintype "bidirectional"))
    )
    (net (code "113") (name "ORIN_SPI_1_SDI") (class "Default")
      (node (ref "B1") (pin "D55") (pinfunction "SPI1_MOSI_D55") (pintype "bidirectional"))
    )
    (net (code "114") (name "ORIN_SPI_1_SDO") (class "Default")
      (node (ref "B1") (pin "A56") (pinfunction "SPI1_MISO_A56") (pintype "bidirectional"))
    )
    (net (code "115") (name "ORIN_SPI_3_CS0") (class "Default")
      (node (ref "B1") (pin "C57") (pinfunction "SPI3_CS0_N_C57") (pintype "bidirectional"))
    )
    (net (code "116") (name "ORIN_SPI_3_CS1") (class "Default")
      (node (ref "B1") (pin "E56") (pinfunction "SPI3_CS1_N_E56") (pintype "bidirectional"))
    )
    (net (code "117") (name "ORIN_SPI_3_SCLK") (class "Default")
      (node (ref "B1") (pin "F55") (pinfunction "SPI3_CLK_F55") (pintype "bidirectional"))
    )
    (net (code "118") (name "ORIN_SPI_3_SDI") (class "Default")
      (node (ref "B1") (pin "G56") (pinfunction "SPI3_MOSI_G56") (pintype "bidirectional"))
    )
    (net (code "119") (name "ORIN_SPI_3_SDO") (class "Default")
      (node (ref "B1") (pin "D56") (pinfunction "SPI3_MISO_D56") (pintype "bidirectional"))
    )
    (net (code "120") (name "ORIN_SYS_RST_IN") (class "Default")
      (node (ref "B1") (pin "L60") (pinfunction "SYS_RESET_N_L60") (pintype "bidirectional"))
      (node (ref "C31") (pin "2") (pinfunction "2_2") (pintype "passive"))
      (node (ref "R115") (pin "1") (pinfunction "1_1") (pintype "passive"))
      (node (ref "R59") (pin "1") (pinfunction "1_1") (pintype "passive"))
    )
    (net (code "121") (name "ORIN_UART1_RX_1V8") (class "Default")
      (node (ref "B1") (pin "K54") (pinfunction "UART1_RX_K54") (pintype "bidirectional"))
    )
    (net (code "122") (name "ORIN_UART1_TX_1V8") (class "Default")
      (node (ref "B1") (pin "K53") (pinfunction "UART1_TX_K53") (pintype "bidirectional"))
    )
    (net (code "123") (name "ORIN_UART3_RX_DEBUG_1V8") (class "Default")
      (node (ref "R98") (pin "2") (pinfunction "2_2") (pintype "passive"))
    )
    (net (code "124") (name "ORIN_UART3_TX_DEBUG_1V8") (class "Default")
      (node (ref "R97") (pin "2") (pinfunction "2_2") (pintype "passive"))
    )
    (net (code "125") (name "ORIN_VCC_CAMERA_EN_1_1") (class "Default")
      (node (ref "B1") (pin "G4") (pinfunction "I2S2_CLK_G4") (pintype "bidirectional"))
    )
    (net (code "126") (name "ORIN_VCC_CAMERA_EN_1_3") (class "Default")
      (node (ref "B1") (pin "E10") (pinfunction "GPIO12_E10") (pintype "bidirectional"))
    )
    (net (code "127") (name "ORIN_VCC_CAMERA_EN_1_5") (class "Default")
      (node (ref "B1") (pin "L15") (pinfunction "GPIO14_L15") (pintype "bidirectional"))
    )
    (net (code "128") (name "ORIN_VCC_CAMERA_EN_1_7") (class "Default")
      (node (ref "B1") (pin "L9") (pinfunction "GPIO28_L9") (pintype "bidirectional"))
    )
    (net (code "129") (name "ORIN_VCC_CAMERA_EN_1_11") (class "Default")
      (node (ref "B1") (pin "C61") (pinfunction "GPIO09_C61") (pintype "bidirectional"))
    )
    (net (code "130") (name "ORIN_VCC_CAMERA_EN_2_1") (class "Default")
      (node (ref "B1") (pin "F6") (pinfunction "I2S2_DIN_F6") (pintype "bidirectional"))
    )
    (net (code "131") (name "ORIN_VCC_CAMERA_EN_2_3") (class "Default")
      (node (ref "B1") (pin "G7") (pinfunction "GPIO13_G7") (pintype "bidirectional"))
    )
    (net (code "132") (name "ORIN_VCC_CAMERA_EN_2_5") (class "Default")
      (node (ref "B1") (pin "E4") (pinfunction "I2S2_FS_E4") (pintype "bidirectional"))
    )
    (net (code "133") (name "ORIN_VCC_CAMERA_EN_2_7") (class "Default")
      (node (ref "B1") (pin "A7") (pinfunction "GPIO29_A7") (pintype "bidirectional"))
    )
    (net (code "134") (name "VCC_3V3") (class "Default")
      (node (ref "R114") (pin "2") (pinfunction "2_2") (pintype "passive"))
    )
    (net (code "135") (name "unconnected-(B1B-GPIO04-PadB59)") (class "Default")
      (node (ref "B1") (pin "B59") (pinfunction "GPIO04_B59") (pintype "bidirectional"))
    )
    (net (code "136") (name "unconnected-(B1B-GPIO11-PadB8)") (class "Default")
      (node (ref "B1") (pin "B8") (pinfunction "GPIO11_B8") (pintype "bidirectional"))
    )
    (net (code "137") (name "unconnected-(B1B-GPIO17-PadA54)") (class "Default")
      (node (ref "B1") (pin "A54") (pinfunction "GPIO17_A54") (pintype "bidirectional"))
    )
    (net (code "138") (name "unconnected-(B1B-GPIO18-PadC55)") (class "Default")
      (node (ref "B1") (pin "C55") (pinfunction "GPIO18_C55") (pintype "bidirectional"))
    )
    (net (code "139") (name "unconnected-(B1B-I2S1_CLK-PadL14)") (class "Default")
      (node (ref "B1") (pin "L14") (pinfunction "I2S1_CLK_L14") (pintype "bidirectional"))
    )
    (net (code "140") (name "unconnected-(B1B-I2S1_FS-PadD8)") (class "Default")
      (node (ref "B1") (pin "D8") (pinfunction "I2S1_FS_D8") (pintype "bidirectional"))
    )
    (net (code "141") (name "unconnected-(B1B-I2S1_SDIN-PadH8)") (class "Default")
      (node (ref "B1") (pin "H8") (pinfunction "I2S1_SDIN_H8") (pintype "bidirectional"))
    )
    (net (code "142") (name "unconnected-(B1B-I2S1_SDOUT-PadC7)") (class "Default")
      (node (ref "B1") (pin "C7") (pinfunction "I2S1_SDOUT_C7") (pintype "bidirectional"))
    )
    (net (code "143") (name "unconnected-(B1B-I2S2_DOUT-PadF5)") (class "Default")
      (node (ref "B1") (pin "F5") (pinfunction "I2S2_DOUT_F5") (pintype "bidirectional"))
    )
    (net (code "144") (name "unconnected-(B1B-I2S3_DIN-PadJ59)") (class "Default")
      (node (ref "B1") (pin "J59") (pinfunction "I2S3_DIN_J59") (pintype "bidirectional"))
    )
    (net (code "145") (name "unconnected-(B1B-I2S3_DOUT-PadK59)") (class "Default")
      (node (ref "B1") (pin "K59") (pinfunction "I2S3_DOUT_K59") (pintype "bidirectional"))
    )
    (net (code "146") (name "unconnected-(B1B-I2S3_SCLK-PadC59)") (class "Default")
      (node (ref "B1") (pin "C59") (pinfunction "I2S3_SCLK_C59") (pintype "bidirectional"))
    )
    (net (code "147") (name "unconnected-(B1B-MCLK01-PadH9)") (class "Default")
      (node (ref "B1") (pin "H9") (pinfunction "MCLK01_H9") (pintype "bidirectional"))
    )
    (net (code "148") (name "unconnected-(B1B-SPI2_CLK-PadE61)") (class "Default")
      (node (ref "B1") (pin "E61") (pinfunction "SPI2_CLK_E61") (pintype "bidirectional"))
    )
    (net (code "149") (name "unconnected-(B1B-SPI2_CS0_N-PadD60)") (class "Default")
      (node (ref "B1") (pin "D60") (pinfunction "SPI2_CS0_N_D60") (pintype "bidirectional"))
    )
    (net (code "150") (name "unconnected-(B1B-SPI2_MISO-PadD62)") (class "Default")
      (node (ref "B1") (pin "D62") (pinfunction "SPI2_MISO_D62") (pintype "bidirectional"))
    )
    (net (code "151") (name "unconnected-(B1B-SPI2_MOSI-PadF60)") (class "Default")
      (node (ref "B1") (pin "F60") (pinfunction "SPI2_MOSI_F60") (pintype "bidirectional"))
    )
    (net (code "152") (name "unconnected-(B1B-UART4_CTS-PadL49)") (class "Default")
      (node (ref "B1") (pin "L49") (pinfunction "UART4_CTS_L49") (pintype "bidirectional"))
    )
    (net (code "153") (name "unconnected-(B1B-UART4_RTS-PadL4)") (class "Default")
      (node (ref "B1") (pin "L4") (pinfunction "UART4_RTS_L4") (pintype "bidirectional"))
    )
    (net (code "154") (name "unconnected-(B1B-UART4_RX-PadL48)") (class "Default")
      (node (ref "B1") (pin "L48") (pinfunction "UART4_RX_L48") (pintype "bidirectional"))
    )
    (net (code "155") (name "unconnected-(B1B-UART4_TX-PadL5)") (class "Default")
      (node (ref "B1") (pin "L5") (pinfunction "UART4_TX_L5") (pintype "bidirectional"))
    )
  )
)
